# Stepper_driver_daughter_board_laser_v5.net
KiCad netlist of a schematic drawn in EAGLE
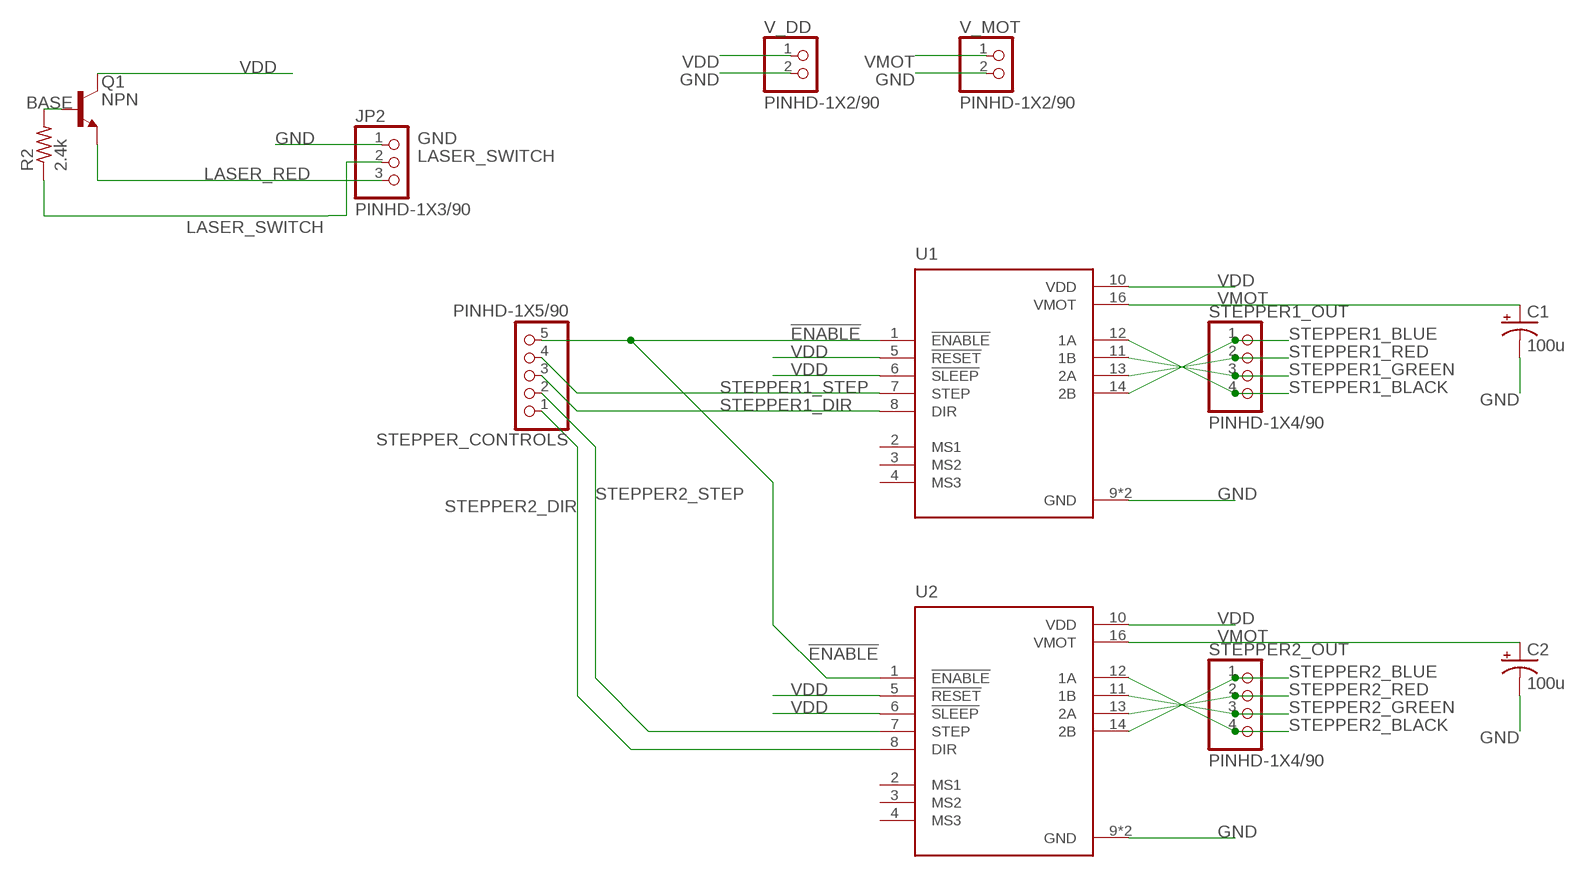
[diagram p0: schematic, sheet 1]

(export (version "E")
  (design (tool "Eeschema 10.0.6"))
  (components
    (comp (ref "C1")
      (value "100u")
      (footprint "eagle-import:E22-6")
      (libsource (lib "eagle-import") (part "CPOL-USE22-6AXIAL"))
    )
    (comp (ref "C2")
      (value "100u")
      (footprint "eagle-import:E22-6")
      (libsource (lib "eagle-import") (part "CPOL-USE22-6AXIAL"))
    )
    (comp (ref "JP2")
      (value "PINHD-1X3/90")
      (footprint "eagle-import:1X03_90")
      (fields (field (name "MANUFACTURER") "Generic"))
      (libsource (lib "eagle-import") (part "PINHD-1X3/90"))
    )
    (comp (ref "Q1")
      (value "NPN")
      (footprint "eagle-import:TO92")
      (libsource (lib "eagle-import") (part "NPNTO92-EBC_"))
    )
    (comp (ref "R2")
      (value "2.4k")
      (footprint "eagle-import:0207_10")
      (libsource (lib "eagle-import") (part "R-US_0207/10"))
    )
    (comp (ref "STEPPER1_OUT")
      (value "PINHD-1X4/90")
      (footprint "eagle-import:1X04_90")
      (fields (field (name "MANUFACTURER") "Generic"))
      (libsource (lib "eagle-import") (part "PINHD-1X4/90"))
    )
    (comp (ref "STEPPER2_OUT")
      (value "PINHD-1X4/90")
      (footprint "eagle-import:1X04_90")
      (fields (field (name "MANUFACTURER") "Generic"))
      (libsource (lib "eagle-import") (part "PINHD-1X4/90"))
    )
    (comp (ref "STEPPER_CONTROLS")
      (value "PINHD-1X5/90")
      (footprint "eagle-import:1X05_90")
      (fields (field (name "MANUFACTURER") "Generic"))
      (libsource (lib "eagle-import") (part "PINHD-1X5/90"))
    )
    (comp (ref "U1")
      (value "A4988_STEPPER_MOTOR_DRIVER_CARRIER")
      (footprint "eagle-import:MODULE_A4988_STEPPER_MOTOR_DRIVER_CARRIER")
      (fields (field (name "MF") "Pololu") (field (name "MP") "A4988 STEPPER MOTOR DRIVER CARRIER"))
      (libsource (lib "eagle-import") (part "A4988_STEPPER_MOTOR_DRIVER_CARRIER"))
    )
    (comp (ref "U2")
      (value "A4988_STEPPER_MOTOR_DRIVER_CARRIER")
      (footprint "eagle-import:MODULE_A4988_STEPPER_MOTOR_DRIVER_CARRIER")
      (fields (field (name "MF") "Pololu") (field (name "MP") "A4988 STEPPER MOTOR DRIVER CARRIER"))
      (libsource (lib "eagle-import") (part "A4988_STEPPER_MOTOR_DRIVER_CARRIER"))
    )
    (comp (ref "V_DD")
      (value "PINHD-1X2/90")
      (footprint "eagle-import:1X02_90")
      (fields (field (name "MANUFACTURER") "Generic"))
      (libsource (lib "eagle-import") (part "PINHD-1X2/90"))
    )
    (comp (ref "V_MOT")
      (value "PINHD-1X2/90")
      (footprint "eagle-import:1X02_90")
      (fields (field (name "MANUFACTURER") "Generic"))
      (libsource (lib "eagle-import") (part "PINHD-1X2/90"))
    )
  )
  (nets
    (net (code "1") (name "/BASE") (class "Default")
      (node (ref "Q1") (pin "2") (pinfunction "B_2") (pintype "passive"))
      (node (ref "R2") (pin "2") (pinfunction "2_2") (pintype "passive"))
    )
    (net (code "2") (name "/GND") (class "Default")
      (node (ref "C1") (pin "-") (pinfunction "-_-") (pintype "passive"))
      (node (ref "C2") (pin "-") (pinfunction "-_-") (pintype "passive"))
      (node (ref "JP2") (pin "1") (pinfunction "1_1") (pintype "passive"))
      (node (ref "U1") (pin "15") (pinfunction "GND_15") (pintype "power_in"))
      (node (ref "U1") (pin "9") (pinfunction "GND_9") (pintype "power_in"))
      (node (ref "U2") (pin "15") (pinfunction "GND_15") (pintype "power_in"))
      (node (ref "U2") (pin "9") (pinfunction "GND_9") (pintype "power_in"))
      (node (ref "V_DD") (pin "2") (pinfunction "2_2") (pintype "passive"))
      (node (ref "V_MOT") (pin "2") (pinfunction "2_2") (pintype "passive"))
    )
    (net (code "3") (name "/LASER_RED") (class "Default")
      (node (ref "JP2") (pin "3") (pinfunction "3_3") (pintype "passive"))
      (node (ref "Q1") (pin "1") (pinfunction "E_1") (pintype "passive"))
    )
    (net (code "4") (name "/LASER_SWITCH") (class "Default")
      (node (ref "JP2") (pin "2") (pinfunction "2_2") (pintype "passive"))
      (node (ref "R2") (pin "1") (pinfunction "1_1") (pintype "passive"))
    )
    (net (code "5") (name "/STEPPER1_BLACK") (class "Default")
      (node (ref "STEPPER1_OUT") (pin "4") (pinfunction "4_4") (pintype "passive"))
      (node (ref "U1") (pin "12") (pinfunction "1A_12") (pintype "output"))
    )
    (net (code "6") (name "/STEPPER1_BLUE") (class "Default")
      (node (ref "STEPPER1_OUT") (pin "1") (pinfunction "1_1") (pintype "passive"))
      (node (ref "U1") (pin "14") (pinfunction "2B_14") (pintype "output"))
    )
    (net (code "7") (name "/STEPPER1_DIR") (class "Default")
      (node (ref "STEPPER_CONTROLS") (pin "3") (pinfunction "3_3") (pintype "passive"))
      (node (ref "U1") (pin "8") (pinfunction "DIR_8") (pintype "input"))
    )
    (net (code "8") (name "/STEPPER1_GREEN") (class "Default")
      (node (ref "STEPPER1_OUT") (pin "3") (pinfunction "3_3") (pintype "passive"))
      (node (ref "U1") (pin "11") (pinfunction "1B_11") (pintype "output"))
    )
    (net (code "9") (name "/STEPPER1_RED") (class "Default")
      (node (ref "STEPPER1_OUT") (pin "2") (pinfunction "2_2") (pintype "passive"))
      (node (ref "U1") (pin "13") (pinfunction "2A_13") (pintype "output"))
    )
    (net (code "10") (name "/STEPPER1_STEP") (class "Default")
      (node (ref "STEPPER_CONTROLS") (pin "4") (pinfunction "4_4") (pintype "passive"))
      (node (ref "U1") (pin "7") (pinfunction "STEP_7") (pintype "input"))
    )
    (net (code "11") (name "/STEPPER2_BLACK") (class "Default")
      (node (ref "STEPPER2_OUT") (pin "4") (pinfunction "4_4") (pintype "passive"))
      (node (ref "U2") (pin "12") (pinfunction "1A_12") (pintype "output"))
    )
    (net (code "12") (name "/STEPPER2_BLUE") (class "Default")
      (node (ref "STEPPER2_OUT") (pin "1") (pinfunction "1_1") (pintype "passive"))
      (node (ref "U2") (pin "14") (pinfunction "2B_14") (pintype "output"))
    )
    (net (code "13") (name "/STEPPER2_DIR") (class "Default")
      (node (ref "STEPPER_CONTROLS") (pin "1") (pinfunction "1_1") (pintype "passive"))
      (node (ref "U2") (pin "8") (pinfunction "DIR_8") (pintype "input"))
    )
    (net (code "14") (name "/STEPPER2_GREEN") (class "Default")
      (node (ref "STEPPER2_OUT") (pin "3") (pinfunction "3_3") (pintype "passive"))
      (node (ref "U2") (pin "11") (pinfunction "1B_11") (pintype "output"))
    )
    (net (code "15") (name "/STEPPER2_RED") (class "Default")
      (node (ref "STEPPER2_OUT") (pin "2") (pinfunction "2_2") (pintype "passive"))
      (node (ref "U2") (pin "13") (pinfunction "2A_13") (pintype "output"))
    )
    (net (code "16") (name "/STEPPER2_STEP") (class "Default")
      (node (ref "STEPPER_CONTROLS") (pin "2") (pinfunction "2_2") (pintype "passive"))
      (node (ref "U2") (pin "7") (pinfunction "STEP_7") (pintype "input"))
    )
    (net (code "17") (name "/VDD") (class "Default")
      (node (ref "Q1") (pin "3") (pinfunction "C_3") (pintype "passive"))
      (node (ref "U1") (pin "10") (pinfunction "VDD_10") (pintype "power_in"))
      (node (ref "U1") (pin "5") (pinfunction "~{RESET}_5") (pintype "input"))
      (node (ref "U1") (pin "6") (pinfunction "~{SLEEP}_6") (pintype "input"))
      (node (ref "U2") (pin "10") (pinfunction "VDD_10") (pintype "power_in"))
      (node (ref "U2") (pin "5") (pinfunction "~{RESET}_5") (pintype "input"))
      (node (ref "U2") (pin "6") (pinfunction "~{SLEEP}_6") (pintype "input"))
      (node (ref "V_DD") (pin "1") (pinfunction "1_1") (pintype "passive"))
    )
    (net (code "18") (name "/VMOT") (class "Default")
      (node (ref "C1") (pin "+") (pinfunction "+_+") (pintype "passive"))
      (node (ref "C2") (pin "+") (pinfunction "+_+") (pintype "passive"))
      (node (ref "U1") (pin "16") (pinfunction "VMOT_16") (pintype "power_in"))
      (node (ref "U2") (pin "16") (pinfunction "VMOT_16") (pintype "power_in"))
      (node (ref "V_MOT") (pin "1") (pinfunction "1_1") (pintype "passive"))
    )
    (net (code "19") (name "/~{ENABLE}") (class "Default")
      (node (ref "STEPPER_CONTROLS") (pin "5") (pinfunction "5_5") (pintype "passive"))
      (node (ref "U1") (pin "1") (pinfunction "~{ENABLE}_1") (pintype "input"))
      (node (ref "U2") (pin "1") (pinfunction "~{ENABLE}_1") (pintype "input"))
    )
    (net (code "20") (name "unconnected-(U1-MS1-Pad2)") (class "Default")
      (node (ref "U1") (pin "2") (pinfunction "MS1_2") (pintype "input"))
    )
    (net (code "21") (name "unconnected-(U1-MS2-Pad3)") (class "Default")
      (node (ref "U1") (pin "3") (pinfunction "MS2_3") (pintype "input"))
    )
    (net (code "22") (name "unconnected-(U1-MS3-Pad4)") (class "Default")
      (node (ref "U1") (pin "4") (pinfunction "MS3_4") (pintype "input"))
    )
    (net (code "23") (name "unconnected-(U2-MS1-Pad2)") (class "Default")
      (node (ref "U2") (pin "2") (pinfunction "MS1_2") (pintype "input"))
    )
    (net (code "24") (name "unconnected-(U2-MS2-Pad3)") (class "Default")
      (node (ref "U2") (pin "3") (pinfunction "MS2_3") (pintype "input"))
    )
    (net (code "25") (name "unconnected-(U2-MS3-Pad4)") (class "Default")
      (node (ref "U2") (pin "4") (pinfunction "MS3_4") (pintype "input"))
    )
  )
)
